# Discharge.net
KiCad netlist of a schematic drawn in Altium Designer
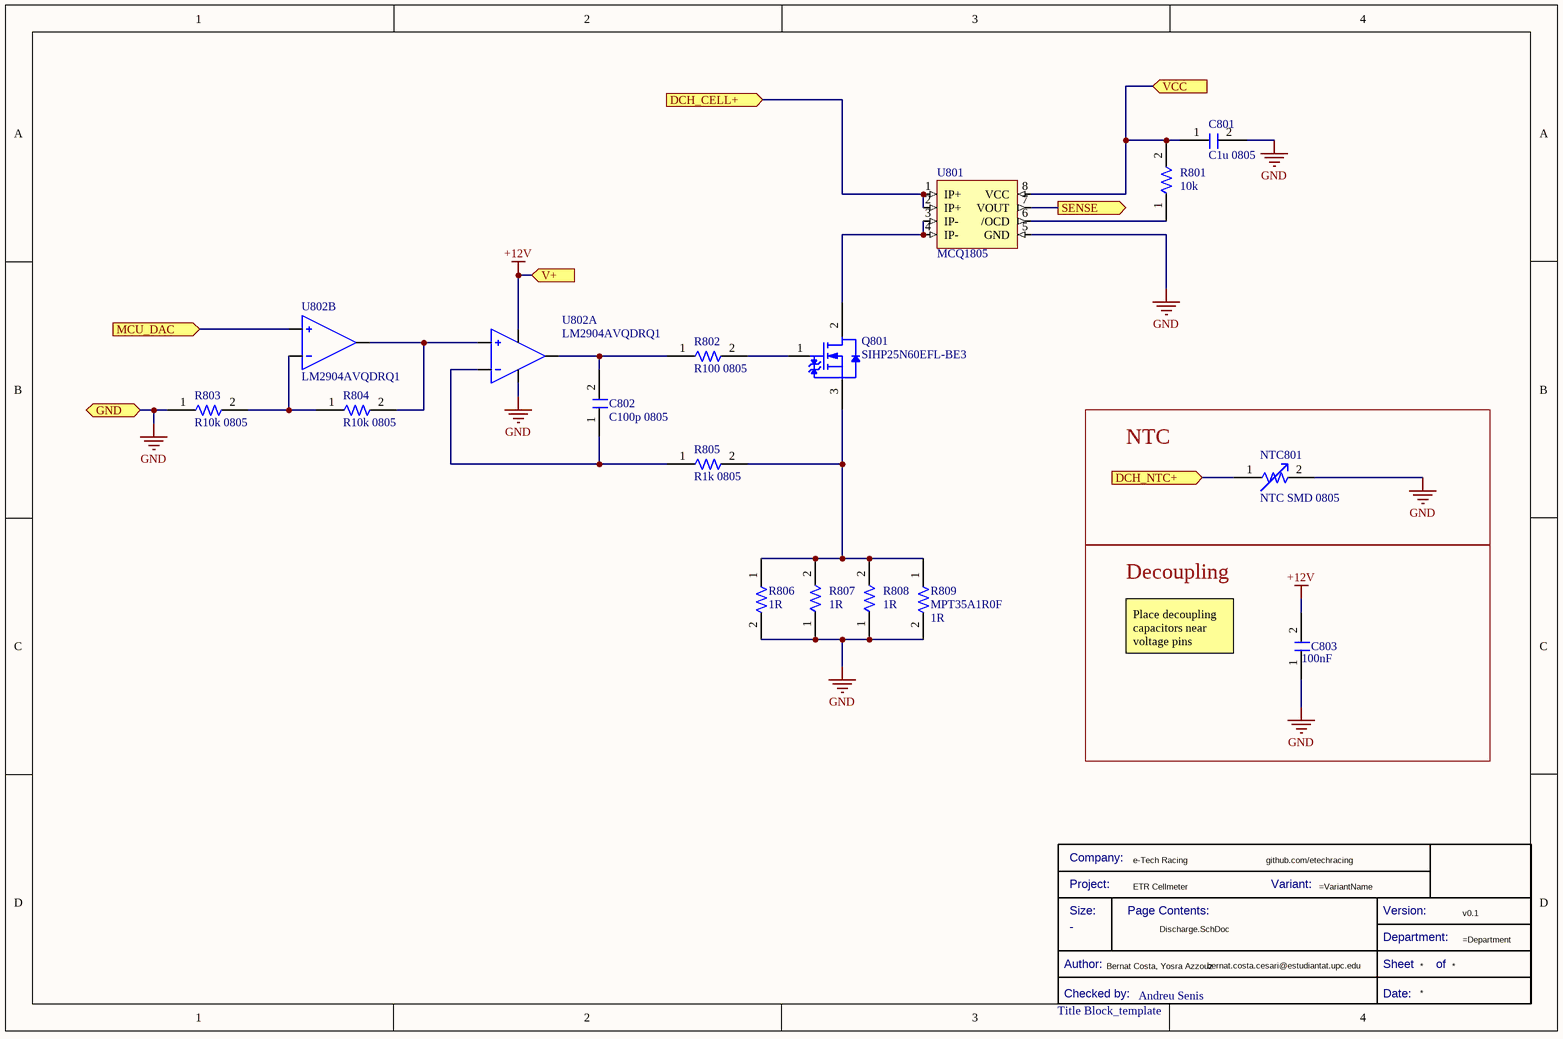
[diagram p0: Discharge.SchDoc]

(export (version "E")
  (design (tool "Eeschema 10.0.6"))
  (components
    (comp (ref "*")
      (value "Title Block_template")
      (description "Standard Title Block")
      (fields
        (field (name "SIZE") "-")
        (field (name ".CREATOR") "GP")
        (field (name ".SCHCHECK") "GP")
        (field (name ".PCBCHECK") "GP")
      )
      (libsource (lib "EMEA- E-Tech Racing- I'Escola d'Enginyeria de Barcelona Est") (part "Title Block_template"))
    )
    (comp (ref "C801")
      (value "C1u 0805")
      (footprint "WCAP-CSGP_0805_L2W1.25H1.25")
      (libsource (lib "EMEA- E-Tech Racing- I'Escola d'Enginyeria de Barcelona Est") (part "C100p-50V-0805FNPC-C0G/NP0"))
    )
    (comp (ref "C802")
      (value "C100p 0805")
      (footprint "C0805FNPC-W")
      (fields
        (field (name "MANUFACTURER") "Wurth Electronics")
        (field (name "TOLERANCE") "5%")
        (field (name "MANUFACTURER PART NUMBER") "885012007057")
        (field (name ".CREATOR") "DR")
      )
      (libsource (lib "EMEA- E-Tech Racing- I'Escola d'Enginyeria de Barcelona Est") (part "C100p-50V-0805FNPC-C0G/NP0"))
    )
    (comp (ref "C803")
      (value "100nF")
      (footprint "C0805FNPC-R")
      (description "Cap, 0.1ΜF, 50V, 10%, X7R, 0805")
      (fields
        (field (name "TOLERANCE") "10%")
        (field (name "Comment") "C100n-50V-0805FNPC-X7R")
        (field (name ".CREATOR") "DR")
      )
      (libsource (lib "EMEA- E-Tech Racing- I'Escola d'Enginyeria de Barcelona Est") (part "C100p-50V-0805FNPC-C0G/NP0"))
    )
    (comp (ref "NTC801")
      (value "NTC SMD 0805")
      (footprint "RESC2012X10N")
      (description "NTC 0805 package 10kR")
      (libsource (lib "EMEA- E-Tech Racing- I'Escola d'Enginyeria de Barcelona Est") (part "0805"))
    )
    (comp (ref "Q801")
      (value "SIHP25N60EFL-BE3")
      (footprint "SIHP25N60EFL-BE3-Footprint-1")
      (description "Power Field-Effect Transistor N Channel THT")
      (libsource (lib "EMEA- E-Tech Racing- I'Escola d'Enginyeria de Barcelona Est") (part "SIHP25N60EFL-BE3"))
    )
    (comp (ref "R801")
      (value "10k")
      (footprint "0805")
      (description "Resistor, 10K, 0.25W, Thick Film, 0805 Rohs Compliant: Yes")
      (fields (field (name "Comment") "R10k_0805_0.25W"))
      (libsource (lib "EMEA- E-Tech Racing- I'Escola d'Enginyeria de Barcelona Est") (part "R9.09K-1206FTK"))
    )
    (comp (ref "R802")
      (value "R100 0805")
      (footprint "R0805FTK")
      (description "Res Thick Film 0805 100 Ohm 1% 1/8W ±100ppm/°C Molded SMD SMD Paper Tape on Plastic Reel")
      (fields (field (name "TOLERANCE") "1%") (field (name ".CREATOR") "DR"))
      (libsource (lib "EMEA- E-Tech Racing- I'Escola d'Enginyeria de Barcelona Est") (part "R9.09K-1206FTK"))
    )
    (comp (ref "R803")
      (value "R10k 0805")
      (footprint "R0805FTK")
      (fields (field (name "TOLERANCE") "5%") (field (name ".CREATOR") "DR"))
      (libsource (lib "EMEA- E-Tech Racing- I'Escola d'Enginyeria de Barcelona Est") (part "R"))
    )
    (comp (ref "R804")
      (value "R10k 0805")
      (footprint "R0805FTK")
      (fields (field (name "TOLERANCE") "5%") (field (name ".CREATOR") "DR"))
      (libsource (lib "EMEA- E-Tech Racing- I'Escola d'Enginyeria de Barcelona Est") (part "R"))
    )
    (comp (ref "R805")
      (value "R1k 0805")
      (footprint "R0805FTK")
      (description "Res Thick Film 0805 1K Ohm 5% 1/8W ±200ppm/°C Molded SMD SMD Paper Tape on Plastic Reel")
      (fields (field (name "TOLERANCE") "5%") (field (name ".CREATOR") "GP"))
      (libsource (lib "EMEA- E-Tech Racing- I'Escola d'Enginyeria de Barcelona Est") (part "R9.09K-1206FTK"))
    )
    (comp (ref "R806")
      (value "MPT35A1R0F")
      (footprint "RTO247")
      (fields
        (field (name "RESISTANCE") "1R")
        (field (name "MANUFACTURER") "TE Connectivity")
        (field (name "MANUFACTURER PART NUMBER") "MPT100C470RF")
      )
      (libsource (lib "EMEA- E-Tech Racing- I'Escola d'Enginyeria de Barcelona Est") (part "MPT35A1R0F"))
    )
    (comp (ref "R807")
      (value "MPT35A1R0F")
      (footprint "RTO247")
      (fields
        (field (name "RESISTANCE") "1R")
        (field (name "MANUFACTURER") "TE Connectivity")
        (field (name "MANUFACTURER PART NUMBER") "MPT100C470RF")
      )
      (libsource (lib "EMEA- E-Tech Racing- I'Escola d'Enginyeria de Barcelona Est") (part "MPT35A1R0F"))
    )
    (comp (ref "R808")
      (value "MPT35A1R0F")
      (footprint "RTO247")
      (fields
        (field (name "RESISTANCE") "1R")
        (field (name "MANUFACTURER") "TE Connectivity")
        (field (name "MANUFACTURER PART NUMBER") "MPT100C470RF")
      )
      (libsource (lib "EMEA- E-Tech Racing- I'Escola d'Enginyeria de Barcelona Est") (part "MPT35A1R0F"))
    )
    (comp (ref "R809")
      (value "MPT35A1R0F")
      (footprint "RTO247")
      (fields
        (field (name "RESISTANCE") "1R")
        (field (name "MANUFACTURER") "TE Connectivity")
        (field (name "MANUFACTURER PART NUMBER") "MPT100C470RF")
      )
      (libsource (lib "EMEA- E-Tech Racing- I'Escola d'Enginyeria de Barcelona Est") (part "MPT35A1R0F"))
    )
    (comp (ref "U801")
      (value "MCQ1805")
      (footprint "SOIC127P600X175-8N")
      (description "3kVRMS Isolated Hall-Effect Current Sensor.")
      (libsource (lib "EMEA- E-Tech Racing- I'Escola d'Enginyeria de Barcelona Est") (part "MCQ1805"))
    )
    (comp (ref "U802")
      (value "LM2904AVQDRQ1")
      (footprint "SOIC127P600X175-8M")
      (description "Operational Amplifier, 2 Func, 7000uV Offset-Max, BIPolar, PDSO8")
      (libsource (lib "EMEA- E-Tech Racing- I'Escola d'Enginyeria de Barcelona Est") (part "LM2904AVQDRQ1"))
    )
  )
  (nets
    (net (code "1") (name "+12V") (class "Default")
      (node (ref "C803") (pin "2") (pinfunction "2_2") (pintype "passive"))
      (node (ref "U802") (pin "8") (pinfunction "VCC+_8") (pintype "power_in"))
    )
    (net (code "2") (name "/DCH_CELL+") (class "Default")
      (node (ref "U801") (pin "1") (pinfunction "IP+_1") (pintype "input"))
      (node (ref "U801") (pin "2") (pinfunction "IP+_2") (pintype "input"))
    )
    (net (code "3") (name "/DCH_NTC+") (class "Default")
      (node (ref "NTC801") (pin "1") (pinfunction "1_1") (pintype "passive"))
    )
    (net (code "4") (name "/MCU_DAC") (class "Default")
      (node (ref "U802") (pin "5") (pinfunction "2IN+_5") (pintype "tri_state"))
    )
    (net (code "5") (name "/SENSE") (class "Default")
      (node (ref "U801") (pin "7") (pinfunction "VOUT_7") (pintype "output"))
    )
    (net (code "6") (name "/VCC") (class "Default")
      (node (ref "C801") (pin "1") (pinfunction "1_1") (pintype "passive"))
      (node (ref "R801") (pin "2") (pinfunction "2_2") (pintype "passive"))
      (node (ref "U801") (pin "8") (pinfunction "VCC_8") (pintype "input"))
    )
    (net (code "7") (name "GND") (class "Default")
      (node (ref "C801") (pin "2") (pinfunction "2_2") (pintype "passive"))
      (node (ref "C803") (pin "1") (pinfunction "1_1") (pintype "passive"))
      (node (ref "NTC801") (pin "2") (pinfunction "2_2") (pintype "passive"))
      (node (ref "R803") (pin "1") (pinfunction "1_1") (pintype "passive"))
      (node (ref "R806") (pin "2") (pinfunction "2_2") (pintype "passive"))
      (node (ref "R807") (pin "1") (pinfunction "1_1") (pintype "passive"))
      (node (ref "R808") (pin "1") (pinfunction "1_1") (pintype "passive"))
      (node (ref "R809") (pin "2") (pinfunction "2_2") (pintype "passive"))
      (node (ref "U801") (pin "5") (pinfunction "GND_5") (pintype "input"))
      (node (ref "U802") (pin "4") (pinfunction "VCC-_4") (pintype "power_in"))
    )
    (net (code "8") (name "Net-(Q801-D)") (class "Default")
      (node (ref "Q801") (pin "2") (pinfunction "D_2") (pintype "passive"))
      (node (ref "U801") (pin "3") (pinfunction "IP-_3") (pintype "input"))
      (node (ref "U801") (pin "4") (pinfunction "IP-_4") (pintype "input"))
    )
    (net (code "9") (name "Net-(Q801-G)") (class "Default")
      (node (ref "Q801") (pin "1") (pinfunction "G_1") (pintype "passive"))
      (node (ref "R802") (pin "2") (pinfunction "2_2") (pintype "passive"))
    )
    (net (code "10") (name "Net-(Q801-S)") (class "Default")
      (node (ref "Q801") (pin "3") (pinfunction "S_3") (pintype "passive"))
      (node (ref "R805") (pin "2") (pinfunction "2_2") (pintype "passive"))
      (node (ref "R806") (pin "1") (pinfunction "1_1") (pintype "passive"))
      (node (ref "R807") (pin "2") (pinfunction "2_2") (pintype "passive"))
      (node (ref "R808") (pin "2") (pinfunction "2_2") (pintype "passive"))
      (node (ref "R809") (pin "1") (pinfunction "1_1") (pintype "passive"))
    )
    (net (code "11") (name "Net-(U801-{slash}OCD)") (class "Default")
      (node (ref "R801") (pin "1") (pinfunction "1_1") (pintype "passive"))
      (node (ref "U801") (pin "6") (pinfunction "/OCD_6") (pintype "output"))
    )
    (net (code "12") (name "Net-(U802A-1IN+)") (class "Default")
      (node (ref "R804") (pin "2") (pinfunction "2_2") (pintype "passive"))
      (node (ref "U802") (pin "3") (pinfunction "1IN+_3") (pintype "tri_state"))
      (node (ref "U802") (pin "7") (pinfunction "OUT2_7") (pintype "passive"))
    )
    (net (code "13") (name "Net-(U802A-1IN-)") (class "Default")
      (node (ref "C802") (pin "1") (pinfunction "1_1") (pintype "passive"))
      (node (ref "R805") (pin "1") (pinfunction "1_1") (pintype "passive"))
      (node (ref "U802") (pin "2") (pinfunction "1IN-_2") (pintype "tri_state"))
    )
    (net (code "14") (name "Net-(U802A-1OUT)") (class "Default")
      (node (ref "C802") (pin "2") (pinfunction "2_2") (pintype "passive"))
      (node (ref "R802") (pin "1") (pinfunction "1_1") (pintype "passive"))
      (node (ref "U802") (pin "1") (pinfunction "1OUT_1") (pintype "passive"))
    )
    (net (code "15") (name "Net-(U802B-2IN-)") (class "Default")
      (node (ref "R803") (pin "2") (pinfunction "2_2") (pintype "passive"))
      (node (ref "R804") (pin "1") (pinfunction "1_1") (pintype "passive"))
      (node (ref "U802") (pin "6") (pinfunction "2IN-_6") (pintype "tri_state"))
    )
  )
)
